# TMR01.net
KiCad netlist of a schematic drawn in EAGLE
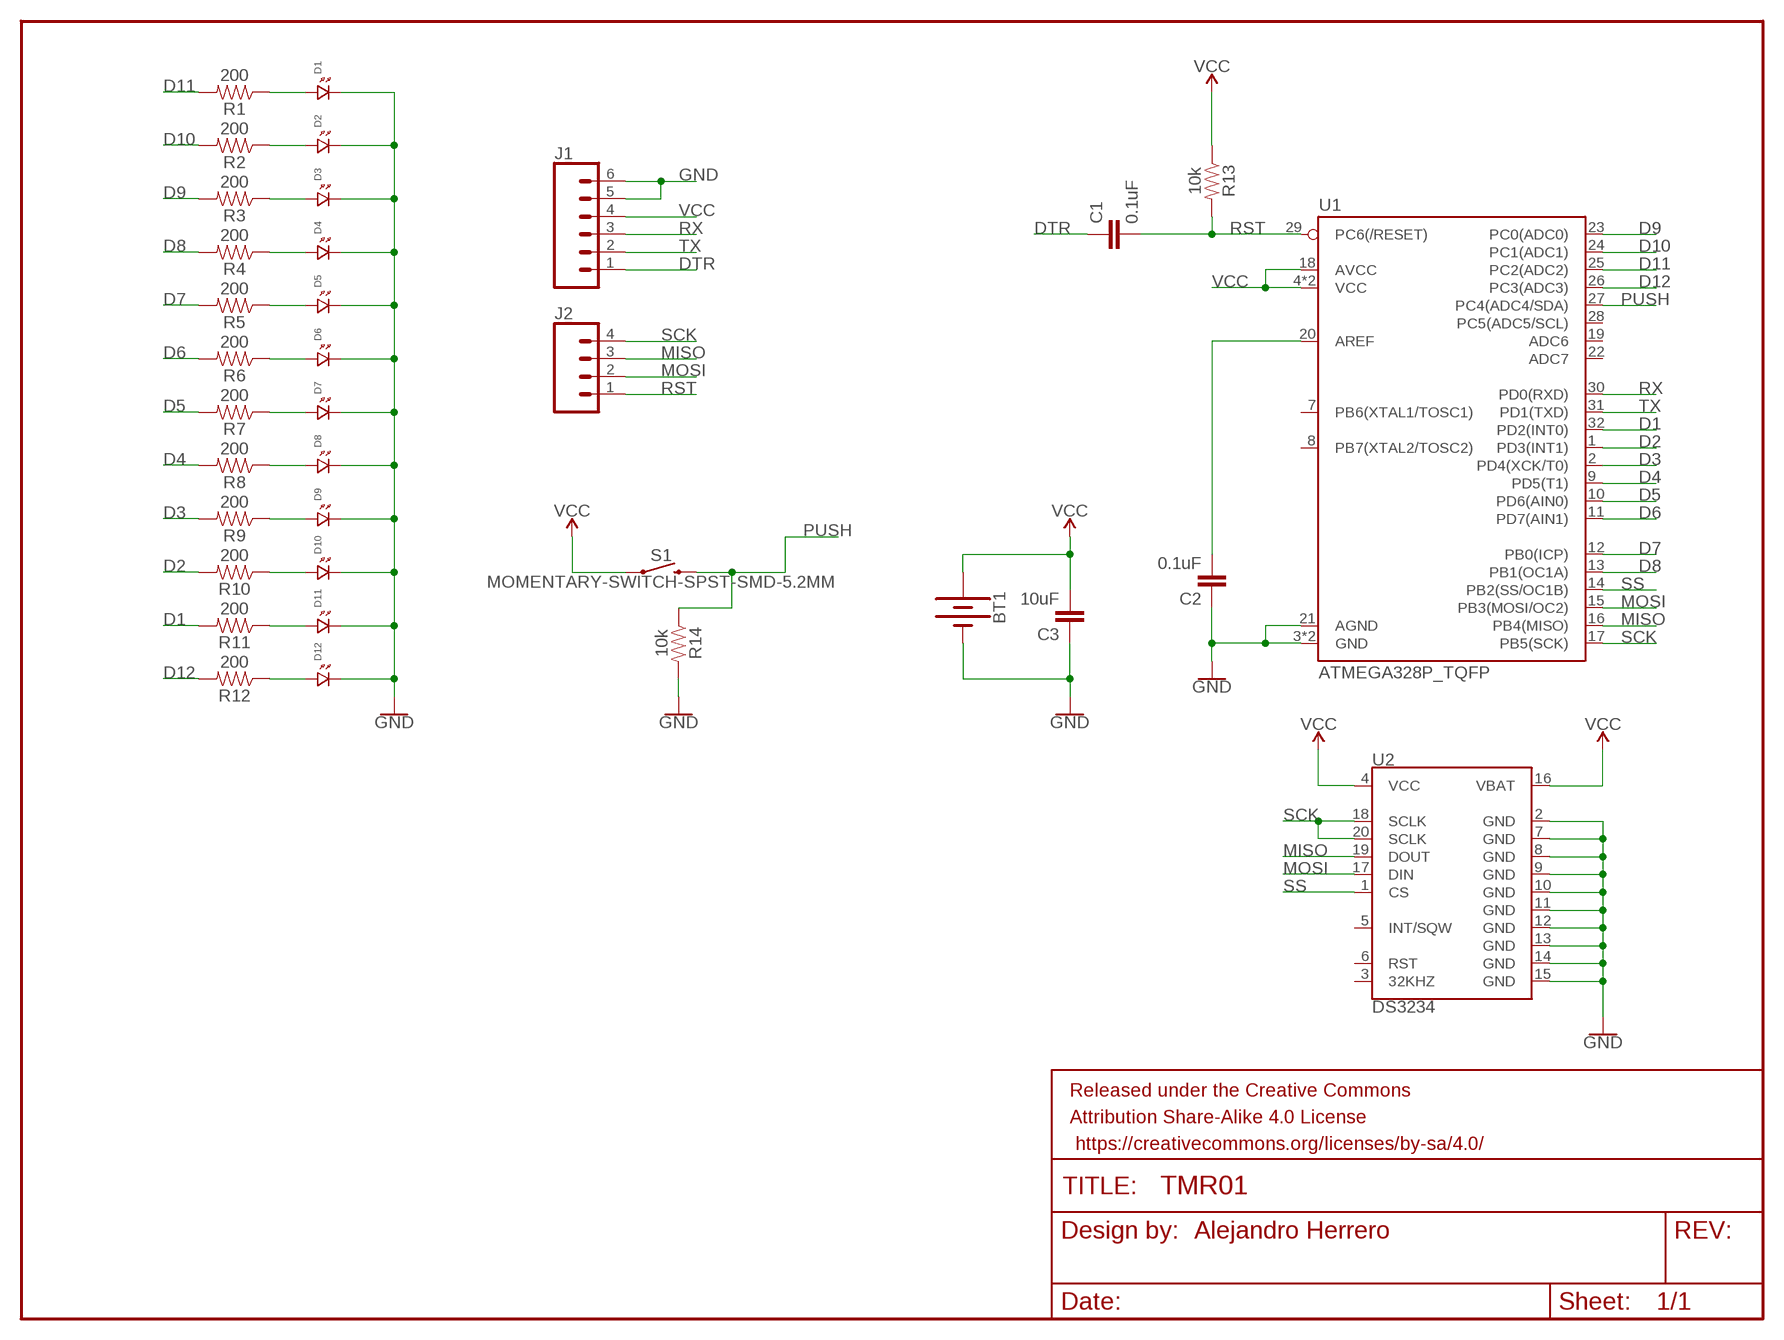
[diagram p0: schematic, sheet 1]

(export (version "E")
  (design (tool "Eeschema 10.0.6"))
  (components
    (comp (ref "BT1")
      (value "BATTERY-20MM_SMD_4LEGS")
      (footprint "eagle-import:BATTCON_20MM_4LEGS")
      (libsource (lib "eagle-import") (part "BATTERY-20MM_SMD_4LEGS"))
    )
    (comp (ref "C1")
      (value "0.1uF")
      (footprint "eagle-import:0402")
      (libsource (lib "eagle-import") (part "0.1UF-0402-16V-10%"))
    )
    (comp (ref "C2")
      (value "0.1uF")
      (footprint "eagle-import:0402")
      (libsource (lib "eagle-import") (part "0.1UF-0402-16V-10%"))
    )
    (comp (ref "C3")
      (value "10uF")
      (footprint "eagle-import:0805")
      (libsource (lib "eagle-import") (part "10UF-0805-10V-10%"))
    )
    (comp (ref "D1")
      (value "LED.0402")
      (footprint "eagle-import:0402.LED")
      (libsource (lib "eagle-import") (part "LED.0402"))
    )
    (comp (ref "D2")
      (value "LED.0402")
      (footprint "eagle-import:0402.LED")
      (libsource (lib "eagle-import") (part "LED.0402"))
    )
    (comp (ref "D3")
      (value "LED.0402")
      (footprint "eagle-import:0402.LED")
      (libsource (lib "eagle-import") (part "LED.0402"))
    )
    (comp (ref "D4")
      (value "LED.0402")
      (footprint "eagle-import:0402.LED")
      (libsource (lib "eagle-import") (part "LED.0402"))
    )
    (comp (ref "D5")
      (value "LED.0402")
      (footprint "eagle-import:0402.LED")
      (libsource (lib "eagle-import") (part "LED.0402"))
    )
    (comp (ref "D6")
      (value "LED.0402")
      (footprint "eagle-import:0402.LED")
      (libsource (lib "eagle-import") (part "LED.0402"))
    )
    (comp (ref "D7")
      (value "LED.0402")
      (footprint "eagle-import:0402.LED")
      (libsource (lib "eagle-import") (part "LED.0402"))
    )
    (comp (ref "D8")
      (value "LED.0402")
      (footprint "eagle-import:0402.LED")
      (libsource (lib "eagle-import") (part "LED.0402"))
    )
    (comp (ref "D9")
      (value "LED.0402")
      (footprint "eagle-import:0402.LED")
      (libsource (lib "eagle-import") (part "LED.0402"))
    )
    (comp (ref "D10")
      (value "LED.0402")
      (footprint "eagle-import:0402.LED")
      (libsource (lib "eagle-import") (part "LED.0402"))
    )
    (comp (ref "D11")
      (value "LED.0402")
      (footprint "eagle-import:0402.LED")
      (libsource (lib "eagle-import") (part "LED.0402"))
    )
    (comp (ref "D12")
      (value "LED.0402")
      (footprint "eagle-import:0402.LED")
      (libsource (lib "eagle-import") (part "LED.0402"))
    )
    (comp (ref "FRAME1")
      (value "FRAME-LETTER")
      (footprint "eagle-import:CREATIVE_COMMONS")
      (libsource (lib "eagle-import") (part "FRAME-LETTER"))
    )
    (comp (ref "J1")
      (value "CONN_06SMD-FEMALE-V2")
      (footprint "eagle-import:1X06-SMD-FEMALE")
      (libsource (lib "eagle-import") (part "CONN_06SMD-FEMALE-V2"))
    )
    (comp (ref "J2")
      (value "CONN_04SMD_RA_FEMALE")
      (footprint "eagle-import:1X04_SMD_RA_FEMALE")
      (libsource (lib "eagle-import") (part "CONN_04SMD_RA_FEMALE"))
    )
    (comp (ref "R1")
      (value "200")
      (footprint "eagle-import:0402")
      (libsource (lib "eagle-import") (part "RESISTOR0402"))
    )
    (comp (ref "R2")
      (value "200")
      (footprint "eagle-import:0402")
      (libsource (lib "eagle-import") (part "RESISTOR0402"))
    )
    (comp (ref "R3")
      (value "200")
      (footprint "eagle-import:0402")
      (libsource (lib "eagle-import") (part "RESISTOR0402"))
    )
    (comp (ref "R4")
      (value "200")
      (footprint "eagle-import:0402")
      (libsource (lib "eagle-import") (part "RESISTOR0402"))
    )
    (comp (ref "R5")
      (value "200")
      (footprint "eagle-import:0402")
      (libsource (lib "eagle-import") (part "RESISTOR0402"))
    )
    (comp (ref "R6")
      (value "200")
      (footprint "eagle-import:0402")
      (libsource (lib "eagle-import") (part "RESISTOR0402"))
    )
    (comp (ref "R7")
      (value "200")
      (footprint "eagle-import:0402")
      (libsource (lib "eagle-import") (part "RESISTOR0402"))
    )
    (comp (ref "R8")
      (value "200")
      (footprint "eagle-import:0402")
      (libsource (lib "eagle-import") (part "RESISTOR0402"))
    )
    (comp (ref "R9")
      (value "200")
      (footprint "eagle-import:0402")
      (libsource (lib "eagle-import") (part "RESISTOR0402"))
    )
    (comp (ref "R10")
      (value "200")
      (footprint "eagle-import:0402")
      (libsource (lib "eagle-import") (part "RESISTOR0402"))
    )
    (comp (ref "R11")
      (value "200")
      (footprint "eagle-import:0402")
      (libsource (lib "eagle-import") (part "RESISTOR0402"))
    )
    (comp (ref "R12")
      (value "200")
      (footprint "eagle-import:0402")
      (libsource (lib "eagle-import") (part "RESISTOR0402"))
    )
    (comp (ref "R13")
      (value "10k")
      (footprint "eagle-import:0402")
      (libsource (lib "eagle-import") (part "RESISTOR0402"))
    )
    (comp (ref "R14")
      (value "10k")
      (footprint "eagle-import:0402")
      (libsource (lib "eagle-import") (part "RESISTOR0402"))
    )
    (comp (ref "S1")
      (value "MOMENTARY-SWITCH-SPST-SMD-5.2MM")
      (footprint "eagle-import:TACTILE_SWITCH_SMD_5.2MM")
      (libsource (lib "eagle-import") (part "MOMENTARY-SWITCH-SPST-SMD-5.2MM"))
    )
    (comp (ref "U1")
      (value "ATMEGA328P_TQFP")
      (footprint "eagle-import:TQFP32-08")
      (libsource (lib "eagle-import") (part "ATMEGA328P_TQFP"))
    )
    (comp (ref "U2")
      (value "DS3234")
      (footprint "eagle-import:SO20-0.3")
      (libsource (lib "eagle-import") (part "DS3234"))
    )
  )
  (nets
    (net (code "1") (name "/D1") (class "Default")
      (node (ref "R11") (pin "2") (pinfunction "2_2") (pintype "passive"))
      (node (ref "U1") (pin "32") (pinfunction "PD2(INT0)_32") (pintype "bidirectional"))
    )
    (net (code "2") (name "/D2") (class "Default")
      (node (ref "R10") (pin "2") (pinfunction "2_2") (pintype "passive"))
      (node (ref "U1") (pin "1") (pinfunction "PD3(INT1)_1") (pintype "bidirectional"))
    )
    (net (code "3") (name "/D3") (class "Default")
      (node (ref "R9") (pin "2") (pinfunction "2_2") (pintype "passive"))
      (node (ref "U1") (pin "2") (pinfunction "PD4(XCK/T0)_2") (pintype "bidirectional"))
    )
    (net (code "4") (name "/D4") (class "Default")
      (node (ref "R8") (pin "2") (pinfunction "2_2") (pintype "passive"))
      (node (ref "U1") (pin "9") (pinfunction "PD5(T1)_9") (pintype "bidirectional"))
    )
    (net (code "5") (name "/D5") (class "Default")
      (node (ref "R7") (pin "2") (pinfunction "2_2") (pintype "passive"))
      (node (ref "U1") (pin "10") (pinfunction "PD6(AIN0)_10") (pintype "bidirectional"))
    )
    (net (code "6") (name "/D6") (class "Default")
      (node (ref "R6") (pin "2") (pinfunction "2_2") (pintype "passive"))
      (node (ref "U1") (pin "11") (pinfunction "PD7(AIN1)_11") (pintype "bidirectional"))
    )
    (net (code "7") (name "/D7") (class "Default")
      (node (ref "R5") (pin "2") (pinfunction "2_2") (pintype "passive"))
      (node (ref "U1") (pin "12") (pinfunction "PB0(ICP)_12") (pintype "bidirectional"))
    )
    (net (code "8") (name "/D8") (class "Default")
      (node (ref "R4") (pin "2") (pinfunction "2_2") (pintype "passive"))
      (node (ref "U1") (pin "13") (pinfunction "PB1(OC1A)_13") (pintype "bidirectional"))
    )
    (net (code "9") (name "/D9") (class "Default")
      (node (ref "R3") (pin "2") (pinfunction "2_2") (pintype "passive"))
      (node (ref "U1") (pin "23") (pinfunction "PC0(ADC0)_23") (pintype "bidirectional"))
    )
    (net (code "10") (name "/D10") (class "Default")
      (node (ref "R2") (pin "2") (pinfunction "2_2") (pintype "passive"))
      (node (ref "U1") (pin "24") (pinfunction "PC1(ADC1)_24") (pintype "bidirectional"))
    )
    (net (code "11") (name "/D11") (class "Default")
      (node (ref "R1") (pin "2") (pinfunction "2_2") (pintype "passive"))
      (node (ref "U1") (pin "25") (pinfunction "PC2(ADC2)_25") (pintype "bidirectional"))
    )
    (net (code "12") (name "/D12") (class "Default")
      (node (ref "R12") (pin "2") (pinfunction "2_2") (pintype "passive"))
      (node (ref "U1") (pin "26") (pinfunction "PC3(ADC3)_26") (pintype "bidirectional"))
    )
    (net (code "13") (name "/DTR") (class "Default")
      (node (ref "C1") (pin "1") (pinfunction "1_1") (pintype "passive"))
      (node (ref "J1") (pin "1") (pinfunction "1_1") (pintype "passive"))
    )
    (net (code "14") (name "/MISO") (class "Default")
      (node (ref "J2") (pin "3") (pinfunction "3_3") (pintype "passive"))
      (node (ref "U1") (pin "16") (pinfunction "PB4(MISO)_16") (pintype "bidirectional"))
      (node (ref "U2") (pin "19") (pinfunction "DOUT_19") (pintype "bidirectional"))
    )
    (net (code "15") (name "/MOSI") (class "Default")
      (node (ref "J2") (pin "2") (pinfunction "2_2") (pintype "passive"))
      (node (ref "U1") (pin "15") (pinfunction "PB3(MOSI/OC2)_15") (pintype "bidirectional"))
      (node (ref "U2") (pin "17") (pinfunction "DIN_17") (pintype "bidirectional"))
    )
    (net (code "16") (name "/PUSH") (class "Default")
      (node (ref "R14") (pin "1") (pinfunction "1_1") (pintype "passive"))
      (node (ref "S1") (pin "3") (pinfunction "2_3") (pintype "passive"))
      (node (ref "U1") (pin "27") (pinfunction "PC4(ADC4/SDA)_27") (pintype "bidirectional"))
    )
    (net (code "17") (name "/RST") (class "Default")
      (node (ref "C1") (pin "2") (pinfunction "2_2") (pintype "passive"))
      (node (ref "J2") (pin "1") (pinfunction "1_1") (pintype "passive"))
      (node (ref "R13") (pin "2") (pinfunction "2_2") (pintype "passive"))
      (node (ref "U1") (pin "29") (pinfunction "PC6(/RESET)_29") (pintype "bidirectional"))
    )
    (net (code "18") (name "/RX") (class "Default")
      (node (ref "J1") (pin "3") (pinfunction "3_3") (pintype "passive"))
      (node (ref "U1") (pin "30") (pinfunction "PD0(RXD)_30") (pintype "bidirectional"))
    )
    (net (code "19") (name "/SCK") (class "Default")
      (node (ref "J2") (pin "4") (pinfunction "4_4") (pintype "passive"))
      (node (ref "U1") (pin "17") (pinfunction "PB5(SCK)_17") (pintype "bidirectional"))
      (node (ref "U2") (pin "18") (pinfunction "SCLK_18") (pintype "bidirectional"))
      (node (ref "U2") (pin "20") (pinfunction "SCLK_20") (pintype "bidirectional"))
    )
    (net (code "20") (name "/SS") (class "Default")
      (node (ref "U1") (pin "14") (pinfunction "PB2(SS/OC1B)_14") (pintype "bidirectional"))
      (node (ref "U2") (pin "1") (pinfunction "CS_1") (pintype "bidirectional"))
    )
    (net (code "21") (name "/TX") (class "Default")
      (node (ref "J1") (pin "2") (pinfunction "2_2") (pintype "passive"))
      (node (ref "U1") (pin "31") (pinfunction "PD1(TXD)_31") (pintype "bidirectional"))
    )
    (net (code "22") (name "GND") (class "Default")
      (node (ref "BT1") (pin "NEGATIVE") (pinfunction "-_NEGATIVE") (pintype "power_in"))
      (node (ref "C2") (pin "1") (pinfunction "1_1") (pintype "passive"))
      (node (ref "C3") (pin "1") (pinfunction "1_1") (pintype "passive"))
      (node (ref "D1") (pin "P$2") (pinfunction "2_P$2") (pintype "bidirectional"))
      (node (ref "D10") (pin "P$2") (pinfunction "2_P$2") (pintype "bidirectional"))
      (node (ref "D11") (pin "P$2") (pinfunction "2_P$2") (pintype "bidirectional"))
      (node (ref "D12") (pin "P$2") (pinfunction "2_P$2") (pintype "bidirectional"))
      (node (ref "D2") (pin "P$2") (pinfunction "2_P$2") (pintype "bidirectional"))
      (node (ref "D3") (pin "P$2") (pinfunction "2_P$2") (pintype "bidirectional"))
      (node (ref "D4") (pin "P$2") (pinfunction "2_P$2") (pintype "bidirectional"))
      (node (ref "D5") (pin "P$2") (pinfunction "2_P$2") (pintype "bidirectional"))
      (node (ref "D6") (pin "P$2") (pinfunction "2_P$2") (pintype "bidirectional"))
      (node (ref "D7") (pin "P$2") (pinfunction "2_P$2") (pintype "bidirectional"))
      (node (ref "D8") (pin "P$2") (pinfunction "2_P$2") (pintype "bidirectional"))
      (node (ref "D9") (pin "P$2") (pinfunction "2_P$2") (pintype "bidirectional"))
      (node (ref "J1") (pin "5") (pinfunction "5_5") (pintype "passive"))
      (node (ref "J1") (pin "6") (pinfunction "6_6") (pintype "passive"))
      (node (ref "R14") (pin "2") (pinfunction "2_2") (pintype "passive"))
      (node (ref "U1") (pin "21") (pinfunction "AGND_21") (pintype "bidirectional"))
      (node (ref "U1") (pin "3") (pinfunction "GND_3") (pintype "bidirectional"))
      (node (ref "U1") (pin "5") (pinfunction "GND_5") (pintype "bidirectional"))
      (node (ref "U2") (pin "10") (pinfunction "GND_10") (pintype "bidirectional"))
      (node (ref "U2") (pin "11") (pinfunction "GND_11") (pintype "bidirectional"))
      (node (ref "U2") (pin "12") (pinfunction "GND_12") (pintype "bidirectional"))
      (node (ref "U2") (pin "13") (pinfunction "GND_13") (pintype "bidirectional"))
      (node (ref "U2") (pin "14") (pinfunction "GND_14") (pintype "bidirectional"))
      (node (ref "U2") (pin "15") (pinfunction "GND_15") (pintype "bidirectional"))
      (node (ref "U2") (pin "2") (pinfunction "GND_2") (pintype "bidirectional"))
      (node (ref "U2") (pin "7") (pinfunction "GND_7") (pintype "bidirectional"))
      (node (ref "U2") (pin "8") (pinfunction "GND_8") (pintype "bidirectional"))
      (node (ref "U2") (pin "9") (pinfunction "GND_9") (pintype "bidirectional"))
    )
    (net (code "23") (name "Net-(D1-1)") (class "Default")
      (node (ref "D1") (pin "P$1") (pinfunction "1_P$1") (pintype "bidirectional"))
      (node (ref "R1") (pin "1") (pinfunction "1_1") (pintype "passive"))
    )
    (net (code "24") (name "Net-(D2-1)") (class "Default")
      (node (ref "D2") (pin "P$1") (pinfunction "1_P$1") (pintype "bidirectional"))
      (node (ref "R2") (pin "1") (pinfunction "1_1") (pintype "passive"))
    )
    (net (code "25") (name "Net-(D3-1)") (class "Default")
      (node (ref "D3") (pin "P$1") (pinfunction "1_P$1") (pintype "bidirectional"))
      (node (ref "R3") (pin "1") (pinfunction "1_1") (pintype "passive"))
    )
    (net (code "26") (name "Net-(D4-1)") (class "Default")
      (node (ref "D4") (pin "P$1") (pinfunction "1_P$1") (pintype "bidirectional"))
      (node (ref "R4") (pin "1") (pinfunction "1_1") (pintype "passive"))
    )
    (net (code "27") (name "Net-(D5-1)") (class "Default")
      (node (ref "D5") (pin "P$1") (pinfunction "1_P$1") (pintype "bidirectional"))
      (node (ref "R5") (pin "1") (pinfunction "1_1") (pintype "passive"))
    )
    (net (code "28") (name "Net-(D6-1)") (class "Default")
      (node (ref "D6") (pin "P$1") (pinfunction "1_P$1") (pintype "bidirectional"))
      (node (ref "R6") (pin "1") (pinfunction "1_1") (pintype "passive"))
    )
    (net (code "29") (name "Net-(D7-1)") (class "Default")
      (node (ref "D7") (pin "P$1") (pinfunction "1_P$1") (pintype "bidirectional"))
      (node (ref "R7") (pin "1") (pinfunction "1_1") (pintype "passive"))
    )
    (net (code "30") (name "Net-(D8-1)") (class "Default")
      (node (ref "D8") (pin "P$1") (pinfunction "1_P$1") (pintype "bidirectional"))
      (node (ref "R8") (pin "1") (pinfunction "1_1") (pintype "passive"))
    )
    (net (code "31") (name "Net-(D9-1)") (class "Default")
      (node (ref "D9") (pin "P$1") (pinfunction "1_P$1") (pintype "bidirectional"))
      (node (ref "R9") (pin "1") (pinfunction "1_1") (pintype "passive"))
    )
    (net (code "32") (name "Net-(D10-1)") (class "Default")
      (node (ref "D10") (pin "P$1") (pinfunction "1_P$1") (pintype "bidirectional"))
      (node (ref "R10") (pin "1") (pinfunction "1_1") (pintype "passive"))
    )
    (net (code "33") (name "Net-(D11-1)") (class "Default")
      (node (ref "D11") (pin "P$1") (pinfunction "1_P$1") (pintype "bidirectional"))
      (node (ref "R11") (pin "1") (pinfunction "1_1") (pintype "passive"))
    )
    (net (code "34") (name "Net-(D12-1)") (class "Default")
      (node (ref "D12") (pin "P$1") (pinfunction "1_P$1") (pintype "bidirectional"))
      (node (ref "R12") (pin "1") (pinfunction "1_1") (pintype "passive"))
    )
    (net (code "35") (name "Net-(U1-AREF)") (class "Default")
      (node (ref "C2") (pin "2") (pinfunction "2_2") (pintype "passive"))
      (node (ref "U1") (pin "20") (pinfunction "AREF_20") (pintype "bidirectional"))
    )
    (net (code "36") (name "VCC") (class "Default")
      (node (ref "BT1") (pin "POSITIVE@1") (pinfunction "+_POSITIVE@1") (pintype "power_in"))
      (node (ref "BT1") (pin "POSITIVE@2") (pinfunction "+_POSITIVE@2") (pintype "power_in"))
      (node (ref "BT1") (pin "POSITIVE@3") (pinfunction "+_POSITIVE@3") (pintype "power_in"))
      (node (ref "BT1") (pin "POSITIVE@4") (pinfunction "+_POSITIVE@4") (pintype "power_in"))
      (node (ref "C3") (pin "2") (pinfunction "2_2") (pintype "passive"))
      (node (ref "J1") (pin "4") (pinfunction "4_4") (pintype "passive"))
      (node (ref "R13") (pin "1") (pinfunction "1_1") (pintype "passive"))
      (node (ref "S1") (pin "1") (pinfunction "1_1") (pintype "passive"))
      (node (ref "U1") (pin "18") (pinfunction "AVCC_18") (pintype "bidirectional"))
      (node (ref "U1") (pin "4") (pinfunction "VCC_4") (pintype "bidirectional"))
      (node (ref "U1") (pin "6") (pinfunction "VCC_6") (pintype "bidirectional"))
      (node (ref "U2") (pin "16") (pinfunction "VBAT_16") (pintype "bidirectional"))
      (node (ref "U2") (pin "4") (pinfunction "VCC_4") (pintype "bidirectional"))
    )
    (net (code "37") (name "unconnected-(U1-ADC6-Pad19)") (class "Default")
      (node (ref "U1") (pin "19") (pinfunction "ADC6_19") (pintype "bidirectional"))
    )
    (net (code "38") (name "unconnected-(U1-ADC7-Pad22)") (class "Default")
      (node (ref "U1") (pin "22") (pinfunction "ADC7_22") (pintype "bidirectional"))
    )
    (net (code "39") (name "unconnected-(U1-PB6(XTAL1{slash}TOSC1)-Pad7)") (class "Default")
      (node (ref "U1") (pin "7") (pinfunction "PB6(XTAL1/TOSC1)_7") (pintype "bidirectional"))
    )
    (net (code "40") (name "unconnected-(U1-PB7(XTAL2{slash}TOSC2)-Pad8)") (class "Default")
      (node (ref "U1") (pin "8") (pinfunction "PB7(XTAL2/TOSC2)_8") (pintype "bidirectional"))
    )
    (net (code "41") (name "unconnected-(U1-PC5(ADC5{slash}SCL)-Pad28)") (class "Default")
      (node (ref "U1") (pin "28") (pinfunction "PC5(ADC5/SCL)_28") (pintype "bidirectional"))
    )
    (net (code "42") (name "unconnected-(U2-32KHZ-Pad3)") (class "Default")
      (node (ref "U2") (pin "3") (pinfunction "32KHZ_3") (pintype "bidirectional"))
    )
    (net (code "43") (name "unconnected-(U2-INT{slash}SQW-Pad5)") (class "Default")
      (node (ref "U2") (pin "5") (pinfunction "INT/SQW_5") (pintype "bidirectional"))
    )
    (net (code "44") (name "unconnected-(U2-RST-Pad6)") (class "Default")
      (node (ref "U2") (pin "6") (pinfunction "RST_6") (pintype "bidirectional"))
    )
  )
)
